# raspi.net
KiCad netlist of a schematic drawn in EAGLE
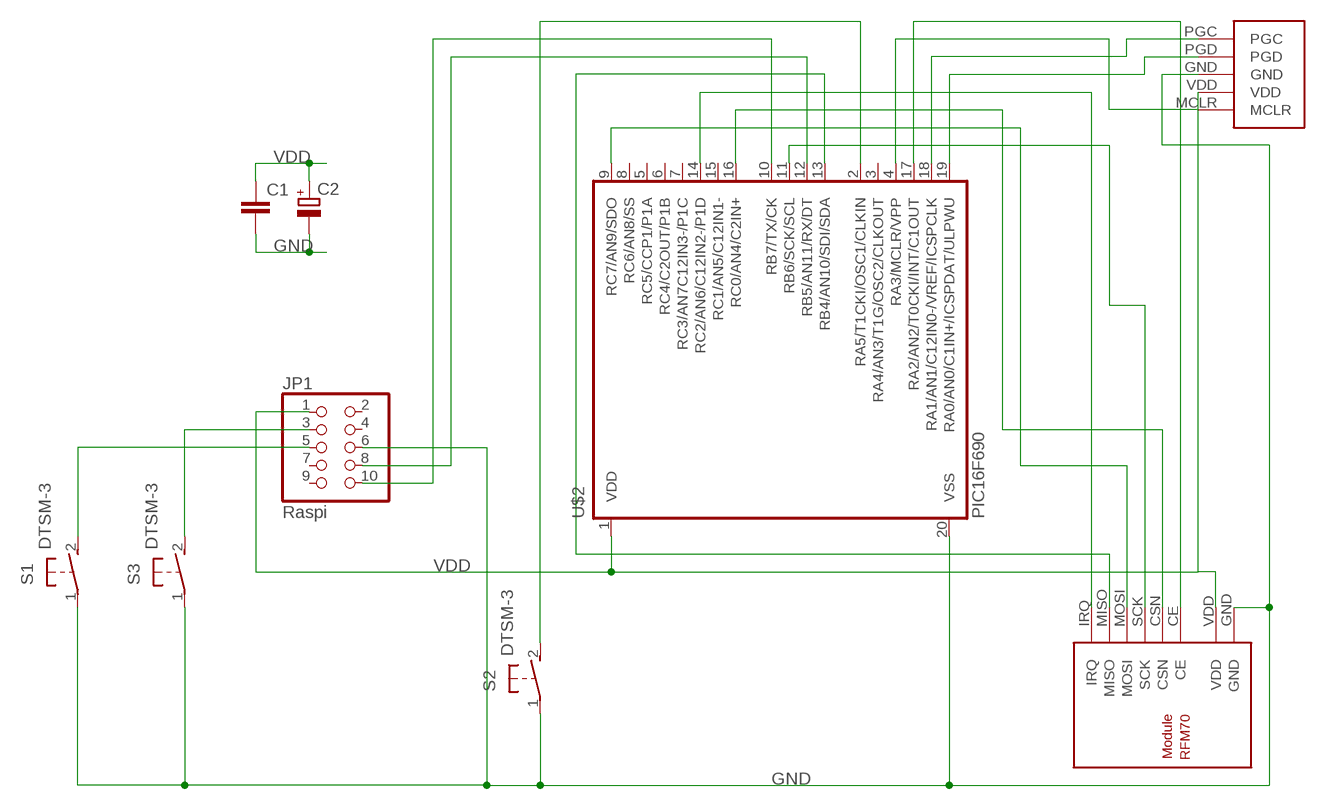
[diagram p0: schematic, sheet 1]

(export (version "E")
  (design (tool "Eeschema 10.0.6"))
  (components
    (comp (ref "C1")
      (value "C-EUC0805")
      (footprint "eagle-import:C0805")
      (libsource (lib "eagle-import") (part "C-EUC0805"))
    )
    (comp (ref "C2")
      (value "CPOL-EUSMCA")
      (footprint "eagle-import:SMC_A")
      (libsource (lib "eagle-import") (part "CPOL-EUSMCA"))
    )
    (comp (ref "JP1")
      (value "Raspi")
      (footprint "eagle-import:2X05")
      (libsource (lib "eagle-import") (part "PINHD-2X5"))
    )
    (comp (ref "S1")
      (value "DTSM-3")
      (footprint "eagle-import:DTSM-3")
      (libsource (lib "eagle-import") (part "DTSM-3"))
    )
    (comp (ref "S2")
      (value "DTSM-3")
      (footprint "eagle-import:DTSM-3")
      (libsource (lib "eagle-import") (part "DTSM-3"))
    )
    (comp (ref "S3")
      (value "DTSM-3")
      (footprint "eagle-import:DTSM-3")
      (libsource (lib "eagle-import") (part "DTSM-3"))
    )
    (comp (ref "U$1")
      (value "RFM70")
      (footprint "eagle-import:RFM70")
      (libsource (lib "eagle-import") (part "RFM70"))
    )
    (comp (ref "U$2")
      (value "PIC16F690")
      (footprint "eagle-import:SSOP20")
      (libsource (lib "eagle-import") (part "PIC16F690"))
    )
    (comp (ref "U$3")
      (value "PROGRAMMINGHEADERDIP")
      (footprint "eagle-import:PROGHEADER")
      (libsource (lib "eagle-import") (part "PROGRAMMINGHEADERDIP"))
    )
  )
  (nets
    (net (code "1") (name "/GND") (class "Default")
      (node (ref "C1") (pin "2") (pinfunction "2_2") (pintype "passive"))
      (node (ref "C2") (pin "-") (pinfunction "-_-") (pintype "passive"))
      (node (ref "JP1") (pin "6") (pinfunction "6_6") (pintype "passive"))
      (node (ref "S1") (pin "1") (pinfunction "1_1") (pintype "passive"))
      (node (ref "S2") (pin "1") (pinfunction "1_1") (pintype "passive"))
      (node (ref "S3") (pin "1") (pinfunction "1_1") (pintype "passive"))
      (node (ref "U$1") (pin "GND") (pinfunction "GND_GND") (pintype "power_in"))
      (node (ref "U$2") (pin "20") (pinfunction "VSS_20") (pintype "power_in"))
      (node (ref "U$3") (pin "GND") (pinfunction "GND_GND") (pintype "power_in"))
    )
    (net (code "2") (name "/VDD") (class "Default")
      (node (ref "C1") (pin "1") (pinfunction "1_1") (pintype "passive"))
      (node (ref "C2") (pin "+") (pinfunction "+_+") (pintype "passive"))
      (node (ref "JP1") (pin "1") (pinfunction "1_1") (pintype "passive"))
      (node (ref "U$1") (pin "VDD") (pinfunction "VDD_VDD") (pintype "power_in"))
      (node (ref "U$2") (pin "1") (pinfunction "VDD_1") (pintype "power_in"))
      (node (ref "U$3") (pin "VDD") (pinfunction "VDD_VDD") (pintype "power_in"))
    )
    (net (code "3") (name "Net-(JP1-Pad3)") (class "Default")
      (node (ref "JP1") (pin "3") (pinfunction "3_3") (pintype "passive"))
      (node (ref "S3") (pin "2") (pinfunction "2_2") (pintype "passive"))
    )
    (net (code "4") (name "Net-(JP1-Pad5)") (class "Default")
      (node (ref "JP1") (pin "5") (pinfunction "5_5") (pintype "passive"))
      (node (ref "S1") (pin "2") (pinfunction "2_2") (pintype "passive"))
    )
    (net (code "5") (name "Net-(U$2-RA0{slash}AN0{slash}C1IN+{slash}ICSPDAT{slash}ULPWU)") (class "Default")
      (node (ref "U$2") (pin "19") (pinfunction "RA0/AN0/C1IN+/ICSPDAT/ULPWU_19") (pintype "bidirectional"))
      (node (ref "U$3") (pin "PGD") (pinfunction "PGD_PGD") (pintype "bidirectional"))
    )
    (net (code "6") (name "Net-(U$2-RA1{slash}AN1{slash}C12IN0-{slash}VREF{slash}ICSPCLK)") (class "Default")
      (node (ref "U$2") (pin "18") (pinfunction "RA1/AN1/C12IN0-/VREF/ICSPCLK_18") (pintype "bidirectional"))
      (node (ref "U$3") (pin "PGC") (pinfunction "PGC_PGC") (pintype "bidirectional"))
    )
    (net (code "7") (name "Net-(U$2-RA2{slash}AN2{slash}T0CKI{slash}INT{slash}C1OUT)") (class "Default")
      (node (ref "U$1") (pin "CE") (pinfunction "CE_CE") (pintype "bidirectional"))
      (node (ref "U$2") (pin "17") (pinfunction "RA2/AN2/T0CKI/INT/C1OUT_17") (pintype "bidirectional"))
    )
    (net (code "8") (name "Net-(U$2-RA3{slash}MCLR{slash}VPP)") (class "Default")
      (node (ref "U$2") (pin "4") (pinfunction "RA3/MCLR/VPP_4") (pintype "bidirectional"))
      (node (ref "U$3") (pin "MCLR") (pinfunction "MCLR_MCLR") (pintype "output"))
    )
    (net (code "9") (name "Net-(U$2-RA5{slash}T1CKI{slash}OSC1{slash}CLKIN)") (class "Default")
      (node (ref "S2") (pin "2") (pinfunction "2_2") (pintype "passive"))
      (node (ref "U$2") (pin "2") (pinfunction "RA5/T1CKI/OSC1/CLKIN_2") (pintype "bidirectional"))
    )
    (net (code "10") (name "Net-(U$2-RB4{slash}AN10{slash}SDI{slash}SDA)") (class "Default")
      (node (ref "U$1") (pin "MISO") (pinfunction "MISO_MISO") (pintype "bidirectional"))
      (node (ref "U$2") (pin "13") (pinfunction "RB4/AN10/SDI/SDA_13") (pintype "bidirectional"))
    )
    (net (code "11") (name "Net-(U$2-RB5{slash}AN11{slash}RX{slash}DT)") (class "Default")
      (node (ref "JP1") (pin "8") (pinfunction "8_8") (pintype "passive"))
      (node (ref "U$2") (pin "12") (pinfunction "RB5/AN11/RX/DT_12") (pintype "bidirectional"))
    )
    (net (code "12") (name "Net-(U$2-RB6{slash}SCK{slash}SCL)") (class "Default")
      (node (ref "U$1") (pin "SCK") (pinfunction "SCK_SCK") (pintype "bidirectional"))
      (node (ref "U$2") (pin "11") (pinfunction "RB6/SCK/SCL_11") (pintype "bidirectional"))
    )
    (net (code "13") (name "Net-(U$2-RB7{slash}TX{slash}CK)") (class "Default")
      (node (ref "JP1") (pin "10") (pinfunction "10_10") (pintype "passive"))
      (node (ref "U$2") (pin "10") (pinfunction "RB7/TX/CK_10") (pintype "bidirectional"))
    )
    (net (code "14") (name "Net-(U$2-RC0{slash}AN4{slash}C2IN+)") (class "Default")
      (node (ref "U$1") (pin "CSN") (pinfunction "CSN_CSN") (pintype "bidirectional"))
      (node (ref "U$2") (pin "16") (pinfunction "RC0/AN4/C2IN+_16") (pintype "bidirectional"))
    )
    (net (code "15") (name "Net-(U$2-RC2{slash}AN6{slash}C12IN2-{slash}P1D)") (class "Default")
      (node (ref "U$1") (pin "IRQ") (pinfunction "IRQ_IRQ") (pintype "bidirectional"))
      (node (ref "U$2") (pin "14") (pinfunction "RC2/AN6/C12IN2-/P1D_14") (pintype "bidirectional"))
    )
    (net (code "16") (name "Net-(U$2-RC7{slash}AN9{slash}SDO)") (class "Default")
      (node (ref "U$1") (pin "MOSI") (pinfunction "MOSI_MOSI") (pintype "bidirectional"))
      (node (ref "U$2") (pin "9") (pinfunction "RC7/AN9/SDO_9") (pintype "bidirectional"))
    )
    (net (code "17") (name "unconnected-(JP1-Pad2)") (class "Default")
      (node (ref "JP1") (pin "2") (pinfunction "2_2") (pintype "passive"))
    )
    (net (code "18") (name "unconnected-(JP1-Pad4)") (class "Default")
      (node (ref "JP1") (pin "4") (pinfunction "4_4") (pintype "passive"))
    )
    (net (code "19") (name "unconnected-(JP1-Pad7)") (class "Default")
      (node (ref "JP1") (pin "7") (pinfunction "7_7") (pintype "passive"))
    )
    (net (code "20") (name "unconnected-(JP1-Pad9)") (class "Default")
      (node (ref "JP1") (pin "9") (pinfunction "9_9") (pintype "passive"))
    )
    (net (code "21") (name "unconnected-(U$2-RA4{slash}AN3{slash}T1G{slash}OSC2{slash}CLKOUT-Pad3)") (class "Default")
      (node (ref "U$2") (pin "3") (pinfunction "RA4/AN3/T1G/OSC2/CLKOUT_3") (pintype "bidirectional"))
    )
    (net (code "22") (name "unconnected-(U$2-RC1{slash}AN5{slash}C12IN1--Pad15)") (class "Default")
      (node (ref "U$2") (pin "15") (pinfunction "RC1/AN5/C12IN1-_15") (pintype "bidirectional"))
    )
    (net (code "23") (name "unconnected-(U$2-RC3{slash}AN7C12IN3-{slash}P1C-Pad7)") (class "Default")
      (node (ref "U$2") (pin "7") (pinfunction "RC3/AN7C12IN3-/P1C_7") (pintype "bidirectional"))
    )
    (net (code "24") (name "unconnected-(U$2-RC4{slash}C2OUT{slash}P1B-Pad6)") (class "Default")
      (node (ref "U$2") (pin "6") (pinfunction "RC4/C2OUT/P1B_6") (pintype "bidirectional"))
    )
    (net (code "25") (name "unconnected-(U$2-RC5{slash}CCP1{slash}P1A-Pad5)") (class "Default")
      (node (ref "U$2") (pin "5") (pinfunction "RC5/CCP1/P1A_5") (pintype "bidirectional"))
    )
    (net (code "26") (name "unconnected-(U$2-RC6{slash}AN8{slash}SS-Pad8)") (class "Default")
      (node (ref "U$2") (pin "8") (pinfunction "RC6/AN8/SS_8") (pintype "bidirectional"))
    )
  )
)
